# sch.net
KiCad netlist of a schematic drawn in EasyEDA
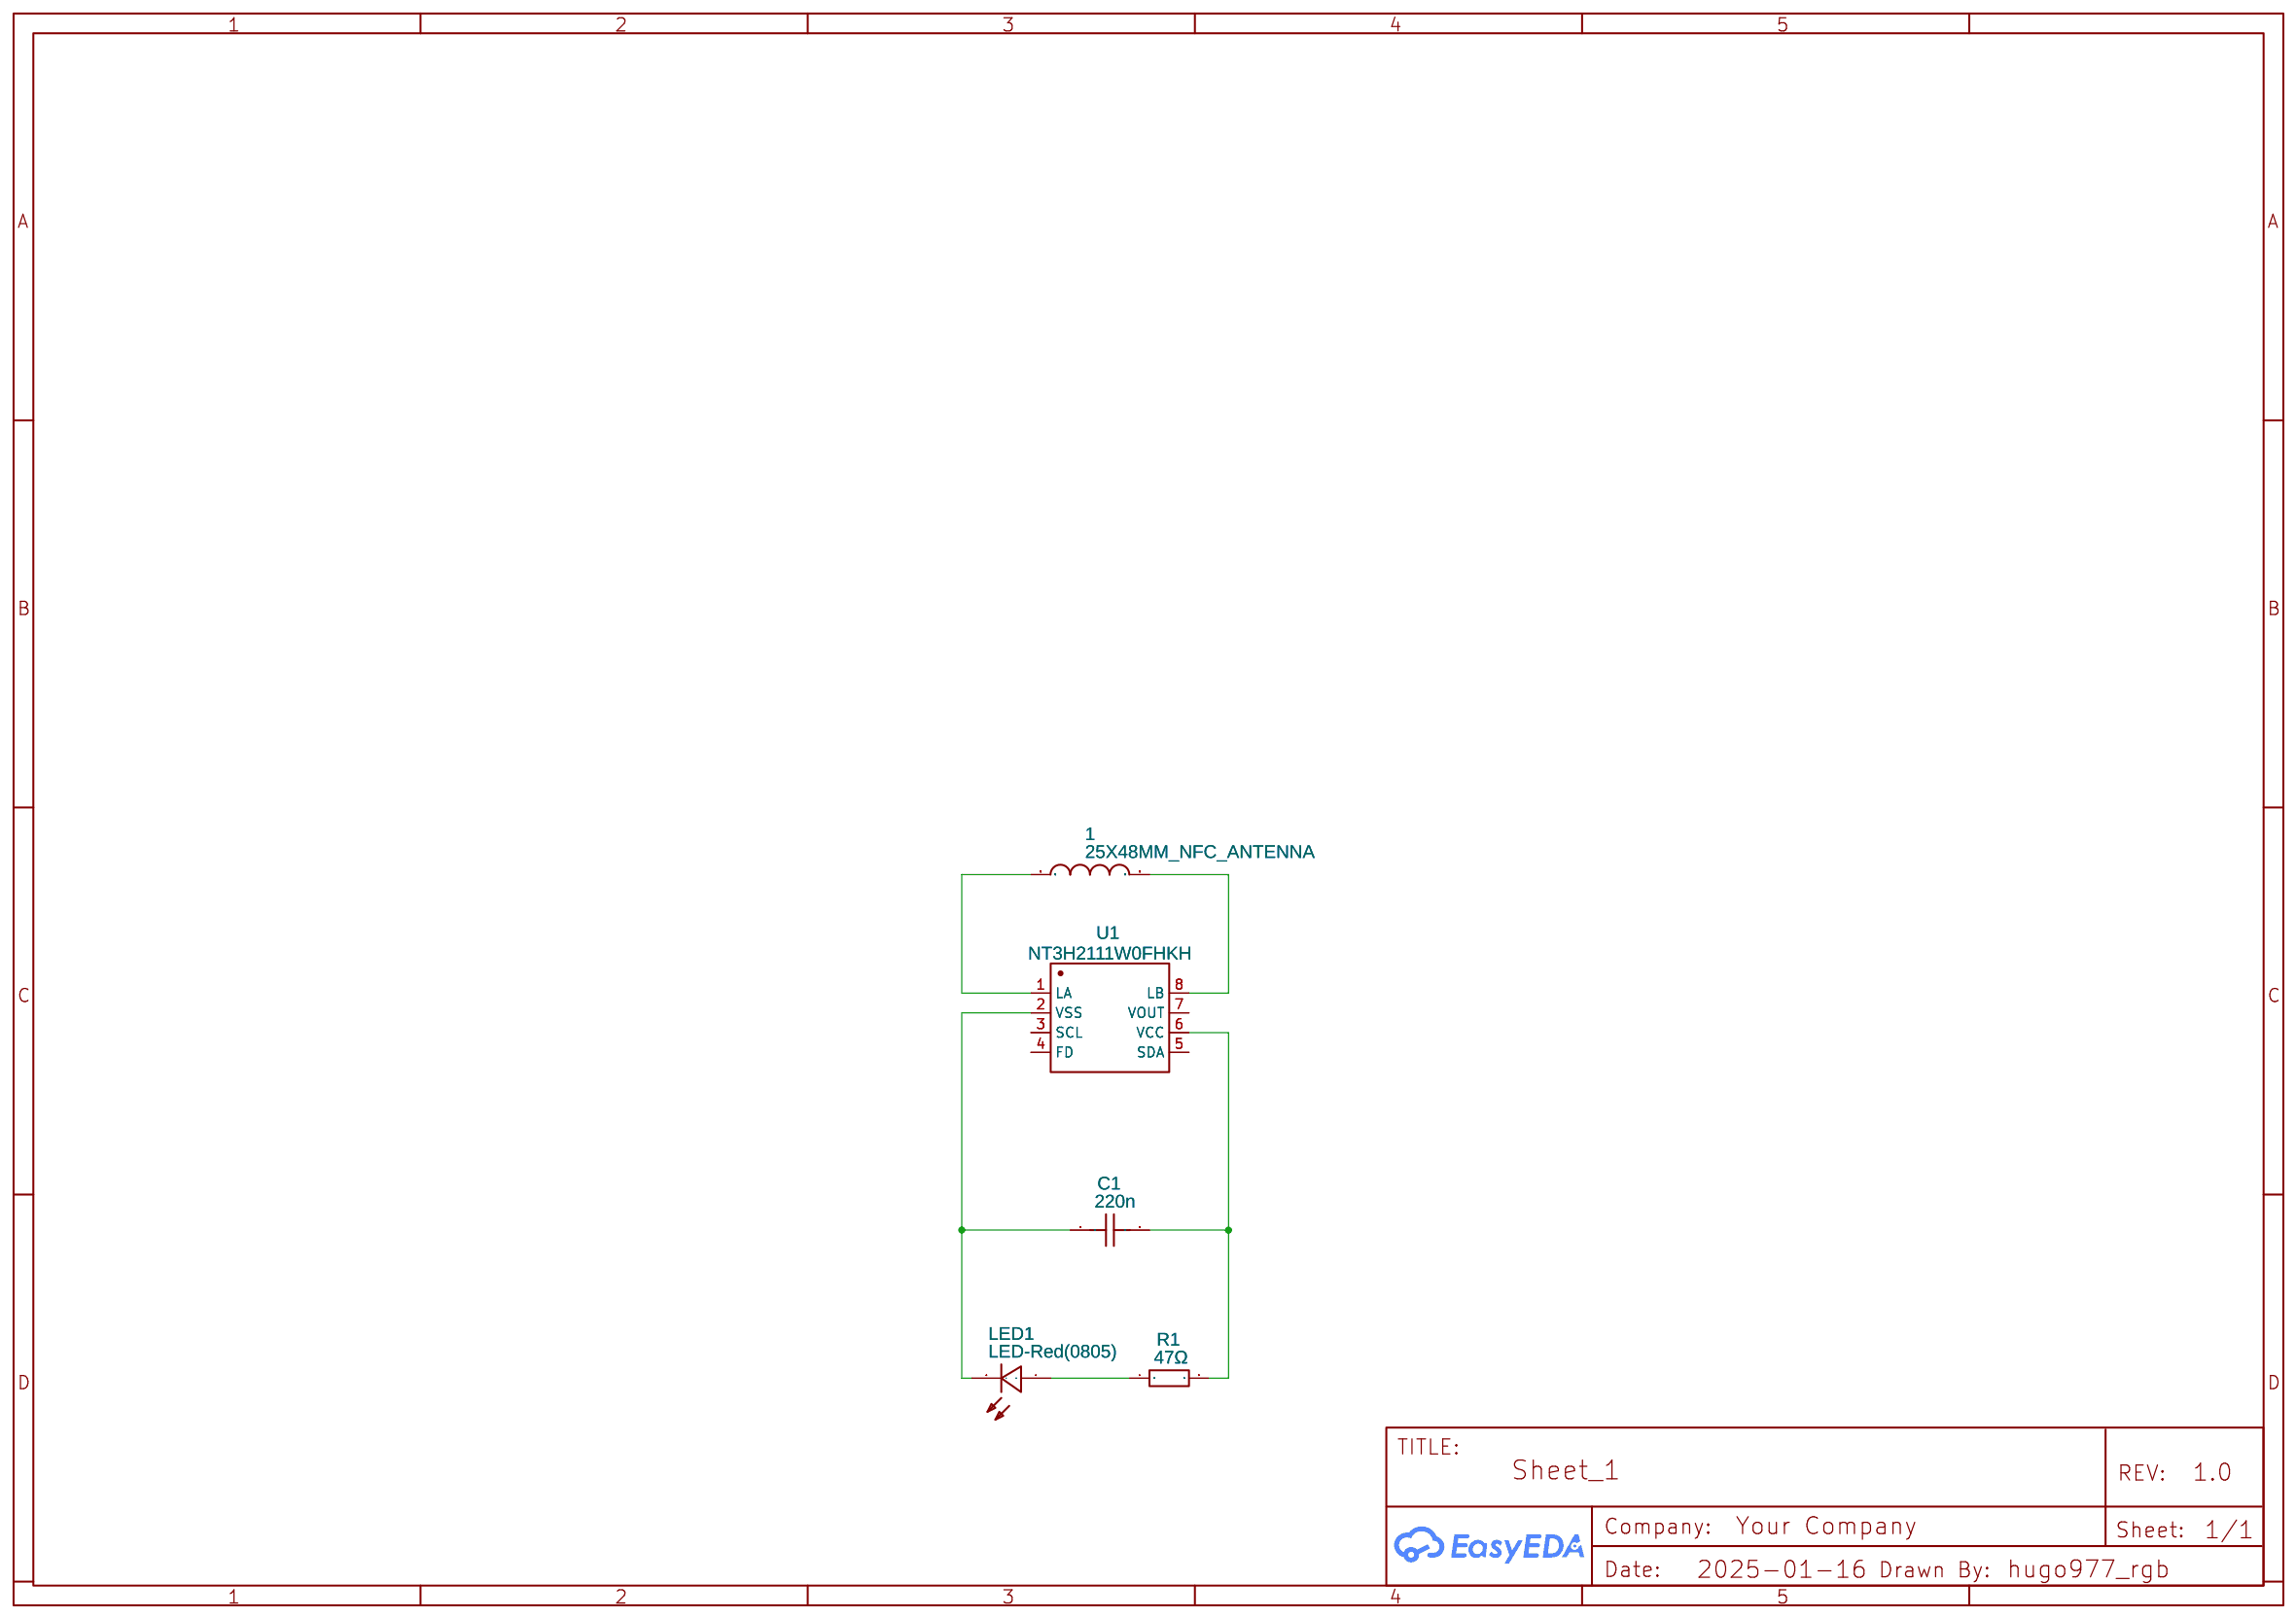
[diagram p0: schematic sheet]

(export (version "E")
  (design (tool "Eeschema 10.0.6"))
  (components
    (comp (ref "1") (value "25X48MM_NFC_ANTENNA") (libsource (lib "") (part "25X48MM_NFC_ANTENNA")))
    (comp (ref "C1") (value "220n") (libsource (lib "") (part "C_0603_US")))
    (comp (ref "LED1")
      (value "LED-Red(0805)")
      (fields
        (field (name "Manufacturer Part") "17-21SURC/S530-A2/TR8")
        (field (name "Manufacturer") "Everlight Elec")
      )
      (libsource (lib "") (part "LED-Red(0805)"))
    )
    (comp (ref "R1")
      (value "47Ω")
      (fields
        (field (name "Manufacturer Part") "0603WAF470JT5E")
        (field (name "Manufacturer") "UNI-ROYAL(厚声)")
      )
      (libsource (lib "") (part "0603WAF470JT5E"))
    )
    (comp (ref "U1")
      (value "NT3H2111W0FHKH")
      (fields (field (name "Manufacturer") "NXP(恩智浦)"))
      (libsource (lib "") (part "NT3H2111W0FHKH"))
    )
  )
  (nets
    (net (code "1") (name "Net-(LED1-+)") (class "Default")
      (node (ref "LED1") (pin "1") (pinfunction "+_1") (pintype "unspecified"))
      (node (ref "R1") (pin "1") (pinfunction "1_1") (pintype "input"))
    )
    (net (code "2") (name "Net-(LED1--)") (class "Default")
      (node (ref "C1") (pin "1") (pinfunction "1_1") (pintype "unspecified"))
      (node (ref "LED1") (pin "2") (pinfunction "-_2") (pintype "unspecified"))
      (node (ref "U1") (pin "2") (pinfunction "VSS_2") (pintype "unspecified"))
    )
    (net (code "3") (name "Net-(U1-LA)") (class "Default")
      (node (ref "1") (pin "P$1") (pinfunction "P$1_P$1") (pintype "bidirectional"))
      (node (ref "U1") (pin "1") (pinfunction "LA_1") (pintype "unspecified"))
    )
    (net (code "4") (name "Net-(U1-LB)") (class "Default")
      (node (ref "1") (pin "P$2") (pinfunction "P$2_P$2") (pintype "bidirectional"))
      (node (ref "U1") (pin "8") (pinfunction "LB_8") (pintype "unspecified"))
    )
    (net (code "5") (name "Net-(U1-VCC)") (class "Default")
      (node (ref "C1") (pin "2") (pinfunction "2_2") (pintype "unspecified"))
      (node (ref "R1") (pin "2") (pinfunction "2_2") (pintype "input"))
      (node (ref "U1") (pin "6") (pinfunction "VCC_6") (pintype "unspecified"))
    )
    (net (code "6") (name "unconnected-(U1-FD-Pad4)") (class "Default")
      (node (ref "U1") (pin "4") (pinfunction "FD_4") (pintype "unspecified"))
    )
    (net (code "7") (name "unconnected-(U1-SCL-Pad3)") (class "Default")
      (node (ref "U1") (pin "3") (pinfunction "SCL_3") (pintype "unspecified"))
    )
    (net (code "8") (name "unconnected-(U1-SDA-Pad5)") (class "Default")
      (node (ref "U1") (pin "5") (pinfunction "SDA_5") (pintype "unspecified"))
    )
    (net (code "9") (name "unconnected-(U1-VOUT-Pad7)") (class "Default")
      (node (ref "U1") (pin "7") (pinfunction "VOUT_7") (pintype "unspecified"))
    )
  )
)
